# ANA_FE_CLK_SYNTH.net
KiCad netlist of a schematic drawn in Altium Designer
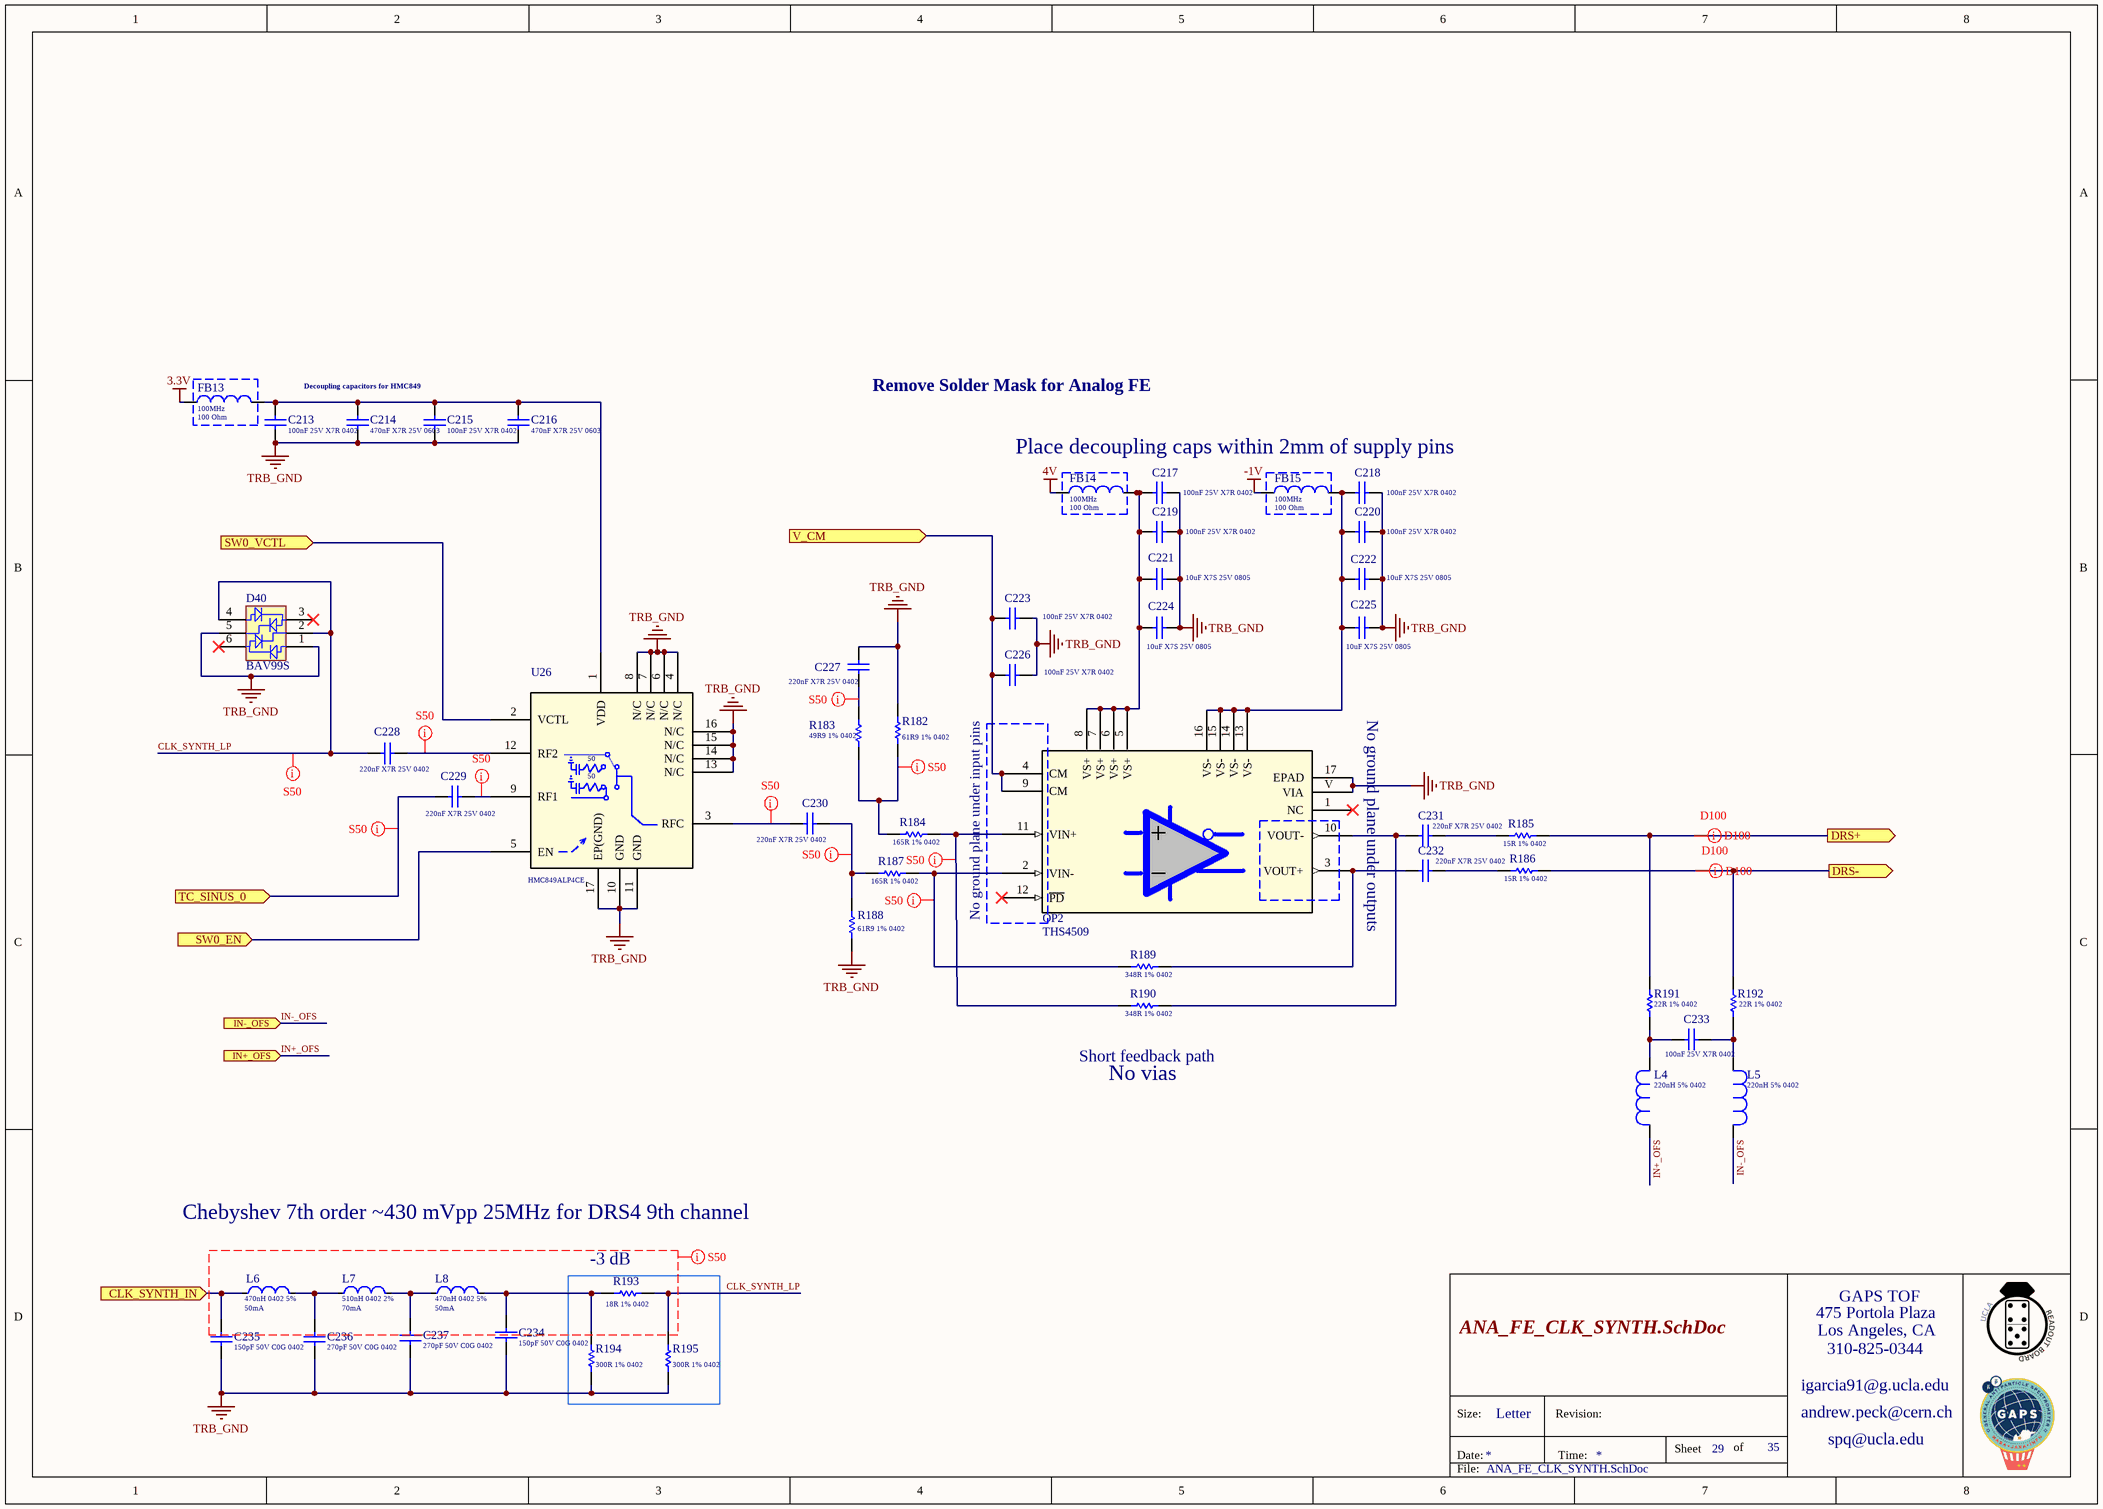
[diagram p0: ANA_FE_CLK_SYNTH.SchDoc]

(export (version "E")
  (design (tool "Eeschema 10.0.6"))
  (components
    (comp (ref "C213")
      (value "Cap_Taiyo_Yuden_TMK105B7104KV-FR_100nF")
      (footprint "Cap_Taiyo_Yuden_TMK105B7104KV-FR_100nF")
      (description "CAP CER 100nF 25V X7R 0402")
      (fields (field (name "CAPACITANCE") "100nF 25V X7R 0402"))
      (libsource (lib "Cap_Taiyo_Yuden_TMK105B7104KV-FR_100nF") (part "Cap_Taiyo_Yuden_TMK105B7104KV-FR_100nF"))
    )
    (comp (ref "C214")
      (value "Cap_Wurth_Electronics_885012206075_470nF")
      (footprint "Cap_Wurth_Electronics_885012206075_470nF")
      (description "CAP CER 470nF 25V X7R 0603")
      (fields (field (name "CAPACITANCE") "470nF X7R 25V 0603"))
      (libsource (lib "Cap_Wurth_Electronics_885012206075_470nF") (part "Cap_Wurth_Electronics_885012206075_470nF"))
    )
    (comp (ref "C215")
      (value "Cap_Taiyo_Yuden_TMK105B7104KV-FR_100nF")
      (footprint "Cap_Taiyo_Yuden_TMK105B7104KV-FR_100nF")
      (description "CAP CER 100nF 25V X7R 0402")
      (fields (field (name "CAPACITANCE") "100nF 25V X7R 0402"))
      (libsource (lib "Cap_Taiyo_Yuden_TMK105B7104KV-FR_100nF") (part "Cap_Taiyo_Yuden_TMK105B7104KV-FR_100nF"))
    )
    (comp (ref "C216")
      (value "Cap_Wurth_Electronics_885012206075_470nF")
      (footprint "Cap_Wurth_Electronics_885012206075_470nF")
      (description "CAP CER 470nF 25V X7R 0603")
      (fields (field (name "CAPACITANCE") "470nF X7R 25V 0603"))
      (libsource (lib "Cap_Wurth_Electronics_885012206075_470nF") (part "Cap_Wurth_Electronics_885012206075_470nF"))
    )
    (comp (ref "C217")
      (value "Cap_Taiyo_Yuden_TMK105B7104KV-FR_100nF")
      (footprint "Cap_Taiyo_Yuden_TMK105B7104KV-FR_100nF")
      (description "CAP CER 100nF 25V X7R 0402")
      (fields (field (name "CAPACITANCE") "100nF 25V X7R 0402"))
      (libsource (lib "Cap_Taiyo_Yuden_TMK105B7104KV-FR_100nF") (part "Cap_Taiyo_Yuden_TMK105B7104KV-FR_100nF"))
    )
    (comp (ref "C218")
      (value "Cap_Taiyo_Yuden_TMK105B7104KV-FR_100nF")
      (footprint "Cap_Taiyo_Yuden_TMK105B7104KV-FR_100nF")
      (description "CAP CER 100nF 25V X7R 0402")
      (fields (field (name "CAPACITANCE") "100nF 25V X7R 0402"))
      (libsource (lib "Cap_Taiyo_Yuden_TMK105B7104KV-FR_100nF") (part "Cap_Taiyo_Yuden_TMK105B7104KV-FR_100nF"))
    )
    (comp (ref "C219")
      (value "Cap_Taiyo_Yuden_TMK105B7104KV-FR_100nF")
      (footprint "Cap_Taiyo_Yuden_TMK105B7104KV-FR_100nF")
      (description "CAP CER 100nF 25V X7R 0402")
      (fields (field (name "CAPACITANCE") "100nF 25V X7R 0402"))
      (libsource (lib "Cap_Taiyo_Yuden_TMK105B7104KV-FR_100nF") (part "Cap_Taiyo_Yuden_TMK105B7104KV-FR_100nF"))
    )
    (comp (ref "C220")
      (value "Cap_Taiyo_Yuden_TMK105B7104KV-FR_100nF")
      (footprint "Cap_Taiyo_Yuden_TMK105B7104KV-FR_100nF")
      (description "CAP CER 100nF 25V X7R 0402")
      (fields (field (name "CAPACITANCE") "100nF 25V X7R 0402"))
      (libsource (lib "Cap_Taiyo_Yuden_TMK105B7104KV-FR_100nF") (part "Cap_Taiyo_Yuden_TMK105B7104KV-FR_100nF"))
    )
    (comp (ref "C221")
      (value "Cap_Murata_ GRM21BC71E106ME11L_10uF")
      (footprint "Cap_Murata_ GRM21BC71E106ME11L_10uF")
      (description "CAP CER 10uF 25V X7R 0805")
      (fields (field (name "CAPACITANCE") "10uF X7S 25V 0805"))
      (libsource (lib "Cap_Murata_ GRM21BC71E106ME11L_10uF") (part "Cap_Murata_ GRM21BC71E106ME11L_10uF"))
    )
    (comp (ref "C222")
      (value "Cap_Murata_ GRM21BC71E106ME11L_10uF")
      (footprint "Cap_Murata_ GRM21BC71E106ME11L_10uF")
      (description "CAP CER 10uF 25V X7R 0805")
      (fields (field (name "CAPACITANCE") "10uF X7S 25V 0805"))
      (libsource (lib "Cap_Murata_ GRM21BC71E106ME11L_10uF") (part "Cap_Murata_ GRM21BC71E106ME11L_10uF"))
    )
    (comp (ref "C223")
      (value "Cap_Taiyo_Yuden_TMK105B7104KV-FR_100nF")
      (footprint "Cap_Taiyo_Yuden_TMK105B7104KV-FR_100nF")
      (description "CAP CER 100nF 25V X7R 0402")
      (fields (field (name "CAPACITANCE") "100nF 25V X7R 0402"))
      (libsource (lib "Cap_Taiyo_Yuden_TMK105B7104KV-FR_100nF") (part "Cap_Taiyo_Yuden_TMK105B7104KV-FR_100nF"))
    )
    (comp (ref "C224")
      (value "Cap_Murata_ GRM21BC71E106ME11L_10uF")
      (footprint "Cap_Murata_ GRM21BC71E106ME11L_10uF")
      (description "CAP CER 10uF 25V X7R 0805")
      (fields (field (name "CAPACITANCE") "10uF X7S 25V 0805"))
      (libsource (lib "Cap_Murata_ GRM21BC71E106ME11L_10uF") (part "Cap_Murata_ GRM21BC71E106ME11L_10uF"))
    )
    (comp (ref "C225")
      (value "Cap_Murata_ GRM21BC71E106ME11L_10uF")
      (footprint "Cap_Murata_ GRM21BC71E106ME11L_10uF")
      (description "CAP CER 10uF 25V X7R 0805")
      (fields (field (name "CAPACITANCE") "10uF X7S 25V 0805"))
      (libsource (lib "Cap_Murata_ GRM21BC71E106ME11L_10uF") (part "Cap_Murata_ GRM21BC71E106ME11L_10uF"))
    )
    (comp (ref "C226")
      (value "Cap_Taiyo_Yuden_TMK105B7104KV-FR_100nF")
      (footprint "Cap_Taiyo_Yuden_TMK105B7104KV-FR_100nF")
      (description "CAP CER 100nF 25V X7R 0402")
      (fields (field (name "CAPACITANCE") "100nF 25V X7R 0402"))
      (libsource (lib "Cap_Taiyo_Yuden_TMK105B7104KV-FR_100nF") (part "Cap_Taiyo_Yuden_TMK105B7104KV-FR_100nF"))
    )
    (comp (ref "C227")
      (value "Cap_TDK_C1608X5R1A106M080AC_220nF")
      (footprint "Cap_TDK_C1608X5R1A106M080AC_220nF")
      (description "CAP CER 220nF 50V X7R 0402")
      (fields (field (name "CAPACITANCE") "220nF X7R 25V 0402"))
      (libsource (lib "Cap_TDK_C1608X5R1A106M080AC_220nF") (part "Cap_TDK_C1608X5R1A106M080AC_220nF"))
    )
    (comp (ref "C228")
      (value "Cap_TDK_C1608X5R1A106M080AC_220nF")
      (footprint "Cap_TDK_C1608X5R1A106M080AC_220nF")
      (description "CAP CER 220nF 50V X7R 0402")
      (fields (field (name "CAPACITANCE") "220nF X7R 25V 0402"))
      (libsource (lib "Cap_TDK_C1608X5R1A106M080AC_220nF") (part "Cap_TDK_C1608X5R1A106M080AC_220nF"))
    )
    (comp (ref "C229")
      (value "Cap_TDK_C1608X5R1A106M080AC_220nF")
      (footprint "Cap_TDK_C1608X5R1A106M080AC_220nF")
      (description "CAP CER 220nF 50V X7R 0402")
      (fields (field (name "CAPACITANCE") "220nF X7R 25V 0402"))
      (libsource (lib "Cap_TDK_C1608X5R1A106M080AC_220nF") (part "Cap_TDK_C1608X5R1A106M080AC_220nF"))
    )
    (comp (ref "C230")
      (value "Cap_TDK_C1608X5R1A106M080AC_220nF")
      (footprint "Cap_TDK_C1608X5R1A106M080AC_220nF")
      (description "CAP CER 220nF 50V X7R 0402")
      (fields (field (name "CAPACITANCE") "220nF X7R 25V 0402"))
      (libsource (lib "Cap_TDK_C1608X5R1A106M080AC_220nF") (part "Cap_TDK_C1608X5R1A106M080AC_220nF"))
    )
    (comp (ref "C231")
      (value "Cap_TDK_C1608X5R1A106M080AC_220nF")
      (footprint "Cap_TDK_C1608X5R1A106M080AC_220nF")
      (description "CAP CER 220nF 50V X7R 0402")
      (fields (field (name "CAPACITANCE") "220nF X7R 25V 0402"))
      (libsource (lib "Cap_TDK_C1608X5R1A106M080AC_220nF") (part "Cap_TDK_C1608X5R1A106M080AC_220nF"))
    )
    (comp (ref "C232")
      (value "Cap_TDK_C1608X5R1A106M080AC_220nF")
      (footprint "Cap_TDK_C1608X5R1A106M080AC_220nF")
      (description "CAP CER 220nF 50V X7R 0402")
      (fields (field (name "CAPACITANCE") "220nF X7R 25V 0402"))
      (libsource (lib "Cap_TDK_C1608X5R1A106M080AC_220nF") (part "Cap_TDK_C1608X5R1A106M080AC_220nF"))
    )
    (comp (ref "C233")
      (value "Cap_Taiyo_Yuden_TMK105B7104KV-FR_100nF")
      (footprint "Cap_Taiyo_Yuden_TMK105B7104KV-FR_100nF")
      (description "CAP CER 100nF 25V X7R 0402")
      (fields (field (name "CAPACITANCE") "100nF 25V X7R 0402"))
      (libsource (lib "Cap_Taiyo_Yuden_TMK105B7104KV-FR_100nF") (part "Cap_Taiyo_Yuden_TMK105B7104KV-FR_100nF"))
    )
    (comp (ref "C234")
      (value "Cap_TDK_CGA2B2C0G2A151J050BE_150pF")
      (footprint "Cap_TDK_CGA2B2C0G2A151J050BE_150pF")
      (description "CAP 150pF 50V C0G ±1% 0402 (1000 Metric) Thickness 1mm SMD")
      (fields (field (name "CAPACITANCE") "150pF 50V C0G 0402"))
      (libsource (lib "Cap_TDK_CGA2B2C0G2A151J050BE_150pF") (part "Cap_TDK_CGA2B2C0G2A151J050BE_150pF"))
    )
    (comp (ref "C235")
      (value "Cap_TDK_CGA2B2C0G2A151J050BE_150pF")
      (footprint "Cap_TDK_CGA2B2C0G2A151J050BE_150pF")
      (description "CAP 150pF 50V C0G ±1% 0402 (1000 Metric) Thickness 1mm SMD")
      (fields (field (name "CAPACITANCE") "150pF 50V C0G 0402"))
      (libsource (lib "Cap_TDK_CGA2B2C0G2A151J050BE_150pF") (part "Cap_TDK_CGA2B2C0G2A151J050BE_150pF"))
    )
    (comp (ref "C236")
      (value "Cap_Murata_GCM1555C1H271FA16D_270pF")
      (footprint "Cap_Murata_GCM1555C1H271FA16D_270pF")
      (description "CAP 270pF 50V C0G ±1% 0402")
      (fields (field (name "CAPACITANCE") "270pF 50V C0G 0402"))
      (libsource (lib "Cap_Murata_GCM1555C1H271FA16D_270pF") (part "Cap_Murata_GCM1555C1H271FA16D_270pF"))
    )
    (comp (ref "C237")
      (value "Cap_Murata_GCM1555C1H271FA16D_270pF")
      (footprint "Cap_Murata_GCM1555C1H271FA16D_270pF")
      (description "CAP 270pF 50V C0G ±1% 0402")
      (fields (field (name "CAPACITANCE") "270pF 50V C0G 0402"))
      (libsource (lib "Cap_Murata_GCM1555C1H271FA16D_270pF") (part "Cap_Murata_GCM1555C1H271FA16D_270pF"))
    )
    (comp (ref "D40")
      (value "BAV99S")
      (footprint "INF-SOT363_V")
      (description "Silicon Switching Diode, SOT363, Reel, Green")
      (fields (field (name "MANUFACTURER") "Infineon"))
      (libsource (lib "Altium Content Vault") (part "INF-D_A1K2C3A4K5C6-6"))
    )
    (comp (ref "FB13")
      (value "742792731")
      (footprint "FB_Wurth_Electronics_742792731_100Ohms")
      (description "FB SMD 100 OHM 25% 1.2A 0402")
      (fields (field (name "MEASURING FREQUENCY") "100MHz") (field (name "IMPEDANCE") "100 Ohm"))
      (libsource (lib "FB_Wurth_Electronics_742792731_100Ohms") (part "FB_Wurth_Electronics_742792731_100Ohms"))
    )
    (comp (ref "FB14")
      (value "742792731")
      (footprint "FB_Wurth_Electronics_742792731_100Ohms")
      (description "FB SMD 100 OHM 25% 1.2A 0402")
      (fields (field (name "MEASURING FREQUENCY") "100MHz") (field (name "IMPEDANCE") "100 Ohm"))
      (libsource (lib "FB_Wurth_Electronics_742792731_100Ohms") (part "FB_Wurth_Electronics_742792731_100Ohms"))
    )
    (comp (ref "FB15")
      (value "742792731")
      (footprint "FB_Wurth_Electronics_742792731_100Ohms")
      (description "FB SMD 100 OHM 25% 1.2A 0402")
      (fields (field (name "MEASURING FREQUENCY") "100MHz") (field (name "IMPEDANCE") "100 Ohm"))
      (libsource (lib "FB_Wurth_Electronics_742792731_100Ohms") (part "FB_Wurth_Electronics_742792731_100Ohms"))
    )
    (comp (ref "L4")
      (value "Ind_TDK_ MLG1005SR22JT000_220nH")
      (footprint "Ind_TDK_ MLG1005SR22JT000_220nH")
      (description "Fixed Inductors .22 UH 5%")
      (fields (field (name "INDUCTANCE") "220nH 5% 0402"))
      (libsource (lib "Ind_TDK_ MLG1005SR22JT000_220nH") (part "Ind_TDK_ MLG1005SR22JT000_220nH"))
    )
    (comp (ref "L5")
      (value "Ind_TDK_ MLG1005SR22JT000_220nH")
      (footprint "Ind_TDK_ MLG1005SR22JT000_220nH")
      (description "Fixed Inductors .22 UH 5%")
      (fields (field (name "INDUCTANCE") "220nH 5% 0402"))
      (libsource (lib "Ind_TDK_ MLG1005SR22JT000_220nH") (part "Ind_TDK_ MLG1005SR22JT000_220nH"))
    )
    (comp (ref "L6")
      (value "470nH 0402 5%")
      (footprint "TDK_MLF1005GR47JT000_0")
      (description "IND 470nH Shielded Multilayer Inductor 50mA 420 mOhm Max 0402 (1005 Metric)")
      (fields
        (field (name "PART NUMBER") "MLF1005GR47JT000")
        (field (name "MANUFACTURER") "TDK")
        (field (name "CURRENT RATING") "50mA")
      )
      (libsource (lib "Ind_TDK_MLF1005GR47JT000_470nH") (part "Ind_TDK_MLF1005GR47JT000"))
    )
    (comp (ref "L7")
      (value "510nH 0402 2%")
      (footprint "TDK_MHQ1005PR51GT000_0")
      (description "IND 510nH Shielded Multilayer Inductor 70mA 10.2 Ohm Max 0402 (1005 Metric)")
      (fields
        (field (name "PART NUMBER") "MHQ1005PR51GT000")
        (field (name "MANUFACTURER") "TDK")
        (field (name "CURRENT RATING") "70mA")
      )
      (libsource (lib "Ind_TDK_MHQ1005PR51GT000_510nH") (part "Ind_TDK_MHQ1005PR51GT000"))
    )
    (comp (ref "L8")
      (value "470nH 0402 5%")
      (footprint "TDK_MLF1005GR47JT000_0")
      (description "IND 470nH Shielded Multilayer Inductor 50mA 420 mOhm Max 0402 (1005 Metric)")
      (fields
        (field (name "PART NUMBER") "MLF1005GR47JT000")
        (field (name "MANUFACTURER") "TDK")
        (field (name "CURRENT RATING") "50mA")
      )
      (libsource (lib "Ind_TDK_MLF1005GR47JT000_470nH") (part "Ind_TDK_MLF1005GR47JT000"))
    )
    (comp (ref "OP2")
      (value "THS4509")
      (footprint "RGT16")
      (description "Differential Amplifier 1 Circuit Differential 16-QFN (3x3)")
      (fields (field (name "MANUFACTURER_PART_NUMBER") "THS4509RGTT"))
      (libsource (lib "THS4509RGTT") (part "THS4509RGTT"))
    )
    (comp (ref "R182")
      (value "61R9 1% 0402")
      (footprint "RESC0402(1005)_L")
      (description "61R9 0.063W 1% 0402 (1005 Metric)  SMD")
      (fields (field (name "TOLERANCE") "1 %") (field (name "POWER") "0.063 W"))
      (libsource (lib "Altium Content Vault") (part "RES"))
    )
    (comp (ref "R183")
      (value "49R9 1% 0402")
      (footprint "RESC0402(1005)_L")
      (description "49R9 0.063W 1% 0402 (1005 Metric)  SMD")
      (fields (field (name "POWER") "0.063 W") (field (name "TOLERANCE") "1 %"))
      (libsource (lib "Altium Content Vault") (part "RES"))
    )
    (comp (ref "R184")
      (value "165R 1% 0402")
      (footprint "RESC0402(1005)_L")
      (description "165R 0.063W 1% 0402 (1005 Metric)  SMD")
      (fields (field (name "POWER") "0.063 W") (field (name "TOLERANCE") "1 %"))
      (libsource (lib "Altium Content Vault") (part "RES"))
    )
    (comp (ref "R185")
      (value "15R 1% 0402")
      (footprint "RESC0402(1005)_L")
      (description "15R 0.063W 1% 0402 (1005 Metric)  SMD")
      (fields (field (name "TOLERANCE") "1 %") (field (name "POWER") "0.063 W"))
      (libsource (lib "Altium Content Vault") (part "RES"))
    )
    (comp (ref "R186")
      (value "15R 1% 0402")
      (footprint "RESC0402(1005)_L")
      (description "15R 0.063W 1% 0402 (1005 Metric)  SMD")
      (fields (field (name "TOLERANCE") "1 %") (field (name "POWER") "0.063 W"))
      (libsource (lib "Altium Content Vault") (part "RES"))
    )
    (comp (ref "R187")
      (value "165R 1% 0402")
      (footprint "RESC0402(1005)_L")
      (description "165R 0.063W 1% 0402 (1005 Metric)  SMD")
      (fields (field (name "POWER") "0.063 W") (field (name "TOLERANCE") "1 %"))
      (libsource (lib "Altium Content Vault") (part "RES"))
    )
    (comp (ref "R188")
      (value "61R9 1% 0402")
      (footprint "RESC0402(1005)_L")
      (description "61R9 0.063W 1% 0402 (1005 Metric)  SMD")
      (fields (field (name "TOLERANCE") "1 %") (field (name "POWER") "0.063 W"))
      (libsource (lib "Altium Content Vault") (part "RES"))
    )
    (comp (ref "R189")
      (value "348R 1% 0402")
      (footprint "RESC0402(1005)_L")
      (description "348R 0.063W 1% 0402 (1005 Metric)  SMD")
      (fields (field (name "TOLERANCE") "1 %") (field (name "POWER") "0.063 W"))
      (libsource (lib "Altium Content Vault") (part "RES"))
    )
    (comp (ref "R190")
      (value "348R 1% 0402")
      (footprint "RESC0402(1005)_L")
      (description "348R 0.063W 1% 0402 (1005 Metric)  SMD")
      (fields (field (name "TOLERANCE") "1 %") (field (name "POWER") "0.063 W"))
      (libsource (lib "Altium Content Vault") (part "RES"))
    )
    (comp (ref "R191")
      (value "22R 1% 0402")
      (footprint "RESC0402(1005)_L")
      (description "22R 0.063W 1% 0402 (1005 Metric)  SMD")
      (fields (field (name "TOLERANCE") "1 %") (field (name "POWER") "0.063 W"))
      (libsource (lib "Altium Content Vault") (part "RES"))
    )
    (comp (ref "R192")
      (value "22R 1% 0402")
      (footprint "RESC0402(1005)_L")
      (description "22R 0.063W 1% 0402 (1005 Metric)  SMD")
      (fields (field (name "TOLERANCE") "1 %") (field (name "POWER") "0.063 W"))
      (libsource (lib "Altium Content Vault") (part "RES"))
    )
    (comp (ref "R193")
      (value "18R 1% 0402")
      (footprint "RESC0402(1005)_L")
      (description "18R 0.063W 1% 0402 (1005 Metric)  SMD")
      (fields (field (name "TOLERANCE") "1 %") (field (name "POWER") "0.063 W"))
      (libsource (lib "Altium Content Vault") (part "RES"))
    )
    (comp (ref "R194")
      (value "300R 1% 0402")
      (footprint "RESC0402(1005)_L")
      (description "300R 0.063W 1% 0402 (1005 Metric)  SMD")
      (fields (field (name "TOLERANCE") "1 %") (field (name "POWER") "0.063 W"))
      (libsource (lib "Altium Content Vault") (part "RES"))
    )
    (comp (ref "R195")
      (value "300R 1% 0402")
      (footprint "RESC0402(1005)_L")
      (description "300R 0.063W 1% 0402 (1005 Metric)  SMD")
      (fields (field (name "TOLERANCE") "1 %") (field (name "POWER") "0.063 W"))
      (libsource (lib "Altium Content Vault") (part "RES"))
    )
    (comp (ref "U26")
      (value "HMC849")
      (footprint "CP_16_40")
      (description "RF Switch ICs DC-6 GHZ Hi Isolation Switch")
      (fields (field (name "MANUFACTURER_PART_NUMBER") "HMC849ALP4CE") (field (name "SERIES") "HMC849ALP4CE"))
      (libsource (lib "HMC849ALP4CE") (part "HMC849ALP4CE"))
    )
  )
  (nets
    (net (code "1") (name "-1V") (class "Default")
      (node (ref "FB15") (pin "1") (pinfunction "1_1") (pintype "passive"))
    )
    (net (code "2") (name "/CLK_SYNTH_IN") (class "Default")
      (node (ref "C235") (pin "2") (pinfunction "2_2") (pintype "passive"))
      (node (ref "L6") (pin "1") (pinfunction "1_1") (pintype "passive"))
    )
    (net (code "3") (name "/CLK_SYNTH_LP") (class "Default")
      (node (ref "C228") (pin "2") (pinfunction "2_2") (pintype "passive"))
      (node (ref "D40") (pin "2") (pinfunction "K2_2") (pintype "passive"))
      (node (ref "D40") (pin "4") (pinfunction "A4_4") (pintype "passive"))
      (node (ref "R193") (pin "2") (pinfunction "2_2") (pintype "passive"))
      (node (ref "R195") (pin "2") (pinfunction "2_2") (pintype "passive"))
    )
    (net (code "4") (name "/DRS+") (class "Default")
      (node (ref "R185") (pin "2") (pinfunction "2_2") (pintype "passive"))
      (node (ref "R191") (pin "2") (pinfunction "2_2") (pintype "passive"))
    )
    (net (code "5") (name "/DRS-") (class "Default")
      (node (ref "R186") (pin "2") (pinfunction "2_2") (pintype "passive"))
      (node (ref "R192") (pin "2") (pinfunction "2_2") (pintype "passive"))
    )
    (net (code "6") (name "/IN+_OFS") (class "Default")
      (node (ref "L4") (pin "2") (pinfunction "2_2") (pintype "passive"))
    )
    (net (code "7") (name "/IN-_OFS") (class "Default")
      (node (ref "L5") (pin "1") (pinfunction "1_1") (pintype "passive"))
    )
    (net (code "8") (name "/SW0_EN") (class "Default")
      (node (ref "U26") (pin "5") (pinfunction "EN_5") (pintype "passive"))
    )
    (net (code "9") (name "/SW0_VCTL") (class "Default")
      (node (ref "U26") (pin "2") (pinfunction "VCTL_2") (pintype "passive"))
    )
    (net (code "10") (name "/TC_SINUS_0") (class "Default")
      (node (ref "C229") (pin "2") (pinfunction "2_2") (pintype "passive"))
    )
    (net (code "11") (name "/V_CM") (class "Default")
      (node (ref "C223") (pin "1") (pinfunction "1_1") (pintype "passive"))
      (node (ref "C226") (pin "1") (pinfunction "1_1") (pintype "passive"))
      (node (ref "OP2") (pin "4") (pinfunction "CM_4") (pintype "passive"))
      (node (ref "OP2") (pin "9") (pinfunction "CM_9") (pintype "passive"))
    )
    (net (code "12") (name "3.3V") (class "Default")
      (node (ref "FB13") (pin "1") (pinfunction "1_1") (pintype "passive"))
    )
    (net (code "13") (name "4V") (class "Default")
      (node (ref "FB14") (pin "1") (pinfunction "1_1") (pintype "passive"))
    )
    (net (code "14") (name "Net-(C217-Pad1)") (class "Default")
      (node (ref "C217") (pin "1") (pinfunction "1_1") (pintype "passive"))
      (node (ref "C219") (pin "1") (pinfunction "1_1") (pintype "passive"))
      (node (ref "C221") (pin "2") (pinfunction "2_2") (pintype "passive"))
      (node (ref "C224") (pin "2") (pinfunction "2_2") (pintype "passive"))
      (node (ref "FB14") (pin "2") (pinfunction "2_2") (pintype "passive"))
      (node (ref "OP2") (pin "5") (pinfunction "VS+_5") (pintype "power_in"))
      (node (ref "OP2") (pin "6") (pinfunction "VS+_6") (pintype "power_in"))
      (node (ref "OP2") (pin "7") (pinfunction "VS+_7") (pintype "power_in"))
      (node (ref "OP2") (pin "8") (pinfunction "VS+_8") (pintype "power_in"))
    )
    (net (code "15") (name "Net-(C218-Pad1)") (class "Default")
      (node (ref "C218") (pin "1") (pinfunction "1_1") (pintype "passive"))
      (node (ref "C220") (pin "1") (pinfunction "1_1") (pintype "passive"))
      (node (ref "C222") (pin "2") (pinfunction "2_2") (pintype "passive"))
      (node (ref "C225") (pin "2") (pinfunction "2_2") (pintype "passive"))
      (node (ref "FB15") (pin "2") (pinfunction "2_2") (pintype "passive"))
      (node (ref "OP2") (pin "13") (pinfunction "VS-_13") (pintype "power_in"))
      (node (ref "OP2") (pin "14") (pinfunction "VS-_14") (pintype "power_in"))
      (node (ref "OP2") (pin "15") (pinfunction "VS-_15") (pintype "power_in"))
      (node (ref "OP2") (pin "16") (pinfunction "VS-_16") (pintype "power_in"))
    )
    (net (code "16") (name "Net-(C227-Pad2)") (class "Default")
      (node (ref "C227") (pin "2") (pinfunction "2_2") (pintype "passive"))
      (node (ref "R183") (pin "2") (pinfunction "2_2") (pintype "passive"))
    )
    (net (code "17") (name "Net-(C230-Pad1)") (class "Default")
      (node (ref "C230") (pin "1") (pinfunction "1_1") (pintype "passive"))
      (node (ref "R187") (pin "1") (pinfunction "1_1") (pintype "passive"))
      (node (ref "R188") (pin "2") (pinfunction "2_2") (pintype "passive"))
    )
    (net (code "18") (name "Net-(C231-Pad1)") (class "Default")
      (node (ref "C231") (pin "1") (pinfunction "1_1") (pintype "passive"))
      (node (ref "R185") (pin "1") (pinfunction "1_1") (pintype "passive"))
    )
    (net (code "19") (name "Net-(C232-Pad1)") (class "Default")
      (node (ref "C232") (pin "1") (pinfunction "1_1") (pintype "passive"))
      (node (ref "R186") (pin "1") (pinfunction "1_1") (pintype "passive"))
    )
    (net (code "20") (name "Net-(C233-Pad1)") (class "Default")
      (node (ref "C233") (pin "1") (pinfunction "1_1") (pintype "passive"))
      (node (ref "L4") (pin "1") (pinfunction "1_1") (pintype "passive"))
      (node (ref "R191") (pin "1") (pinfunction "1_1") (pintype "passive"))
    )
    (net (code "21") (name "Net-(C233-Pad2)") (class "Default")
      (node (ref "C233") (pin "2") (pinfunction "2_2") (pintype "passive"))
      (node (ref "L5") (pin "2") (pinfunction "2_2") (pintype "passive"))
      (node (ref "R192") (pin "1") (pinfunction "1_1") (pintype "passive"))
    )
    (net (code "22") (name "Net-(C234-Pad2)") (class "Default")
      (node (ref "C234") (pin "2") (pinfunction "2_2") (pintype "passive"))
      (node (ref "L8") (pin "2") (pinfunction "2_2") (pintype "passive"))
      (node (ref "R193") (pin "1") (pinfunction "1_1") (pintype "passive"))
      (node (ref "R194") (pin "2") (pinfunction "2_2") (pintype "passive"))
    )
    (net (code "23") (name "Net-(C236-Pad2)") (class "Default")
      (node (ref "C236") (pin "2") (pinfunction "2_2") (pintype "passive"))
      (node (ref "L6") (pin "2") (pinfunction "2_2") (pintype "passive"))
      (node (ref "L7") (pin "1") (pinfunction "1_1") (pintype "passive"))
    )
    (net (code "24") (name "Net-(C237-Pad2)") (class "Default")
      (node (ref "C237") (pin "2") (pinfunction "2_2") (pintype "passive"))
      (node (ref "L7") (pin "2") (pinfunction "2_2") (pintype "passive"))
      (node (ref "L8") (pin "1") (pinfunction "1_1") (pintype "passive"))
    )
    (net (code "25") (name "Net-(OP2-VIN+)") (class "Default")
      (node (ref "OP2") (pin "11") (pinfunction "VIN+_11") (pintype "input"))
      (node (ref "R184") (pin "2") (pinfunction "2_2") (pintype "passive"))
      (node (ref "R190") (pin "1") (pinfunction "1_1") (pintype "passive"))
    )
    (net (code "26") (name "Net-(OP2-VIN-)") (class "Default")
      (node (ref "OP2") (pin "2") (pinfunction "VIN-_2") (pintype "input"))
      (node (ref "R187") (pin "2") (pinfunction "2_2") (pintype "passive"))
      (node (ref "R189") (pin "1") (pinfunction "1_1") (pintype "passive"))
    )
    (net (code "27") (name "Net-(OP2-VOUT+)") (class "Default")
      (node (ref "C232") (pin "2") (pinfunction "2_2") (pintype "passive"))
      (node (ref "OP2") (pin "3") (pinfunction "VOUT+_3") (pintype "output"))
      (node (ref "R189") (pin "2") (pinfunction "2_2") (pintype "passive"))
    )
    (net (code "28") (name "Net-(OP2-VOUT-)") (class "Default")
      (node (ref "C231") (pin "2") (pinfunction "2_2") (pintype "passive"))
      (node (ref "OP2") (pin "10") (pinfunction "VOUT-_10") (pintype "output"))
      (node (ref "R190") (pin "2") (pinfunction "2_2") (pintype "passive"))
    )
    (net (code "29") (name "Net-(R182-Pad1)") (class "Default")
      (node (ref "R182") (pin "1") (pinfunction "1_1") (pintype "passive"))
      (node (ref "R183") (pin "1") (pinfunction "1_1") (pintype "passive"))
      (node (ref "R184") (pin "1") (pinfunction "1_1") (pintype "passive"))
    )
    (net (code "30") (name "Net-(U26-RF1)") (class "Default")
      (node (ref "C229") (pin "1") (pinfunction "1_1") (pintype "passive"))
      (node (ref "U26") (pin "9") (pinfunction "RF1_9") (pintype "passive"))
    )
    (net (code "31") (name "Net-(U26-RF2)") (class "Default")
      (node (ref "C228") (pin "1") (pinfunction "1_1") (pintype "passive"))
      (node (ref "U26") (pin "12") (pinfunction "RF2_12") (pintype "passive"))
    )
    (net (code "32") (name "Net-(U26-RFC)") (class "Default")
      (node (ref "C230") (pin "2") (pinfunction "2_2") (pintype "passive"))
      (node (ref "U26") (pin "3") (pinfunction "RFC_3") (pintype "passive"))
    )
    (net (code "33") (name "Net-(U26-VDD)") (class "Default")
      (node (ref "C213") (pin "2") (pinfunction "2_2") (pintype "passive"))
      (node (ref "C214") (pin "1") (pinfunction "1_1") (pintype "passive"))
      (node (ref "C215") (pin "2") (pinfunction "2_2") (pintype "passive"))
      (node (ref "C216") (pin "1") (pinfunction "1_1") (pintype "passive"))
      (node (ref "FB13") (pin "2") (pinfunction "2_2") (pintype "passive"))
      (node (ref "U26") (pin "1") (pinfunction "VDD_1") (pintype "passive"))
    )
    (net (code "34") (name "TRB_GND") (class "Default")
      (node (ref "C213") (pin "1") (pinfunction "1_1") (pintype "passive"))
      (node (ref "C214") (pin "2") (pinfunction "2_2") (pintype "passive"))
      (node (ref "C215") (pin "1") (pinfunction "1_1") (pintype "passive"))
      (node (ref "C216") (pin "2") (pinfunction "2_2") (pintype "passive"))
      (node (ref "C217") (pin "2") (pinfunction "2_2") (pintype "passive"))
      (node (ref "C218") (pin "2") (pinfunction "2_2") (pintype "passive"))
      (node (ref "C219") (pin "2") (pinfunction "2_2") (pintype "passive"))
      (node (ref "C220") (pin "2") (pinfunction "2_2") (pintype "passive"))
      (node (ref "C221") (pin "1") (pinfunction "1_1") (pintype "passive"))
      (node (ref "C222") (pin "1") (pinfunction "1_1") (pintype "passive"))
      (node (ref "C223") (pin "2") (pinfunction "2_2") (pintype "passive"))
      (node (ref "C224") (pin "1") (pinfunction "1_1") (pintype "passive"))
      (node (ref "C225") (pin "1") (pinfunction "1_1") (pintype "passive"))
      (node (ref "C226") (pin "2") (pinfunction "2_2") (pintype "passive"))
      (node (ref "C227") (pin "1") (pinfunction "1_1") (pintype "passive"))
      (node (ref "C234") (pin "1") (pinfunction "1_1") (pintype "passive"))
      (node (ref "C235") (pin "1") (pinfunction "1_1") (pintype "passive"))
      (node (ref "C236") (pin "1") (pinfunction "1_1") (pintype "passive"))
      (node (ref "C237") (pin "1") (pinfunction "1_1") (pintype "passive"))
      (node (ref "D40") (pin "1") (pinfunction "A1_1") (pintype "passive"))
      (node (ref "D40") (pin "5") (pinfunction "K5_5") (pintype "passive"))
      (node (ref "OP2") (pin "17") (pinfunction "EPAD_17") (pintype "passive"))
      (node (ref "OP2") (pin "V") (pinfunction "VIA_V") (pintype "passive"))
      (node (ref "R182") (pin "2") (pinfunction "2_2") (pintype "passive"))
      (node (ref "R188") (pin "1") (pinfunction "1_1") (pintype "passive"))
      (node (ref "R194") (pin "1") (pinfunction "1_1") (pintype "passive"))
      (node (ref "R195") (pin "1") (pinfunction "1_1") (pintype "passive"))
      (node (ref "U26") (pin "10") (pinfunction "GND_10") (pintype "passive"))
      (node (ref "U26") (pin "11") (pinfunction "GND_11") (pintype "passive"))
      (node (ref "U26") (pin "13") (pinfunction "N/C_13") (pintype "passive"))
      (node (ref "U26") (pin "14") (pinfunction "N/C_14") (pintype "passive"))
      (node (ref "U26") (pin "15") (pinfunction "N/C_15") (pintype "passive"))
      (node (ref "U26") (pin "16") (pinfunction "N/C_16") (pintype "passive"))
      (node (ref "U26") (pin "17") (pinfunction "EP(GND)_17") (pintype "passive"))
      (node (ref "U26") (pin "4") (pinfunction "N/C_4") (pintype "passive"))
      (node (ref "U26") (pin "6") (pinfunction "N/C_6") (pintype "passive"))
      (node (ref "U26") (pin "7") (pinfunction "N/C_7") (pintype "passive"))
      (node (ref "U26") (pin "8") (pinfunction "N/C_8") (pintype "passive"))
    )
    (net (code "35") (name "unconnected-(D40-C3-Pad3)") (class "Default")
      (node (ref "D40") (pin "3") (pinfunction "C3_3") (pintype "passive+no_connect"))
    )
    (net (code "36") (name "unconnected-(D40-C6-Pad6)") (class "Default")
      (node (ref "D40") (pin "6") (pinfunction "C6_6") (pintype "passive+no_connect"))
    )
    (net (code "37") (name "unconnected-(OP2-NC-Pad1)") (class "Default")
      (node (ref "OP2") (pin "1") (pinfunction "NC_1") (pintype "passive+no_connect"))
    )
    (net (code "38") (name "unconnected-(OP2-~{PD}-Pad12)") (class "Default")
      (node (ref "OP2") (pin "12") (pinfunction "~{PD}_12") (pintype "input+no_connect"))
    )
  )
)
